# E75-2G4M20S-BEE-1_1.net
KiCad netlist of a schematic drawn in EAGLE
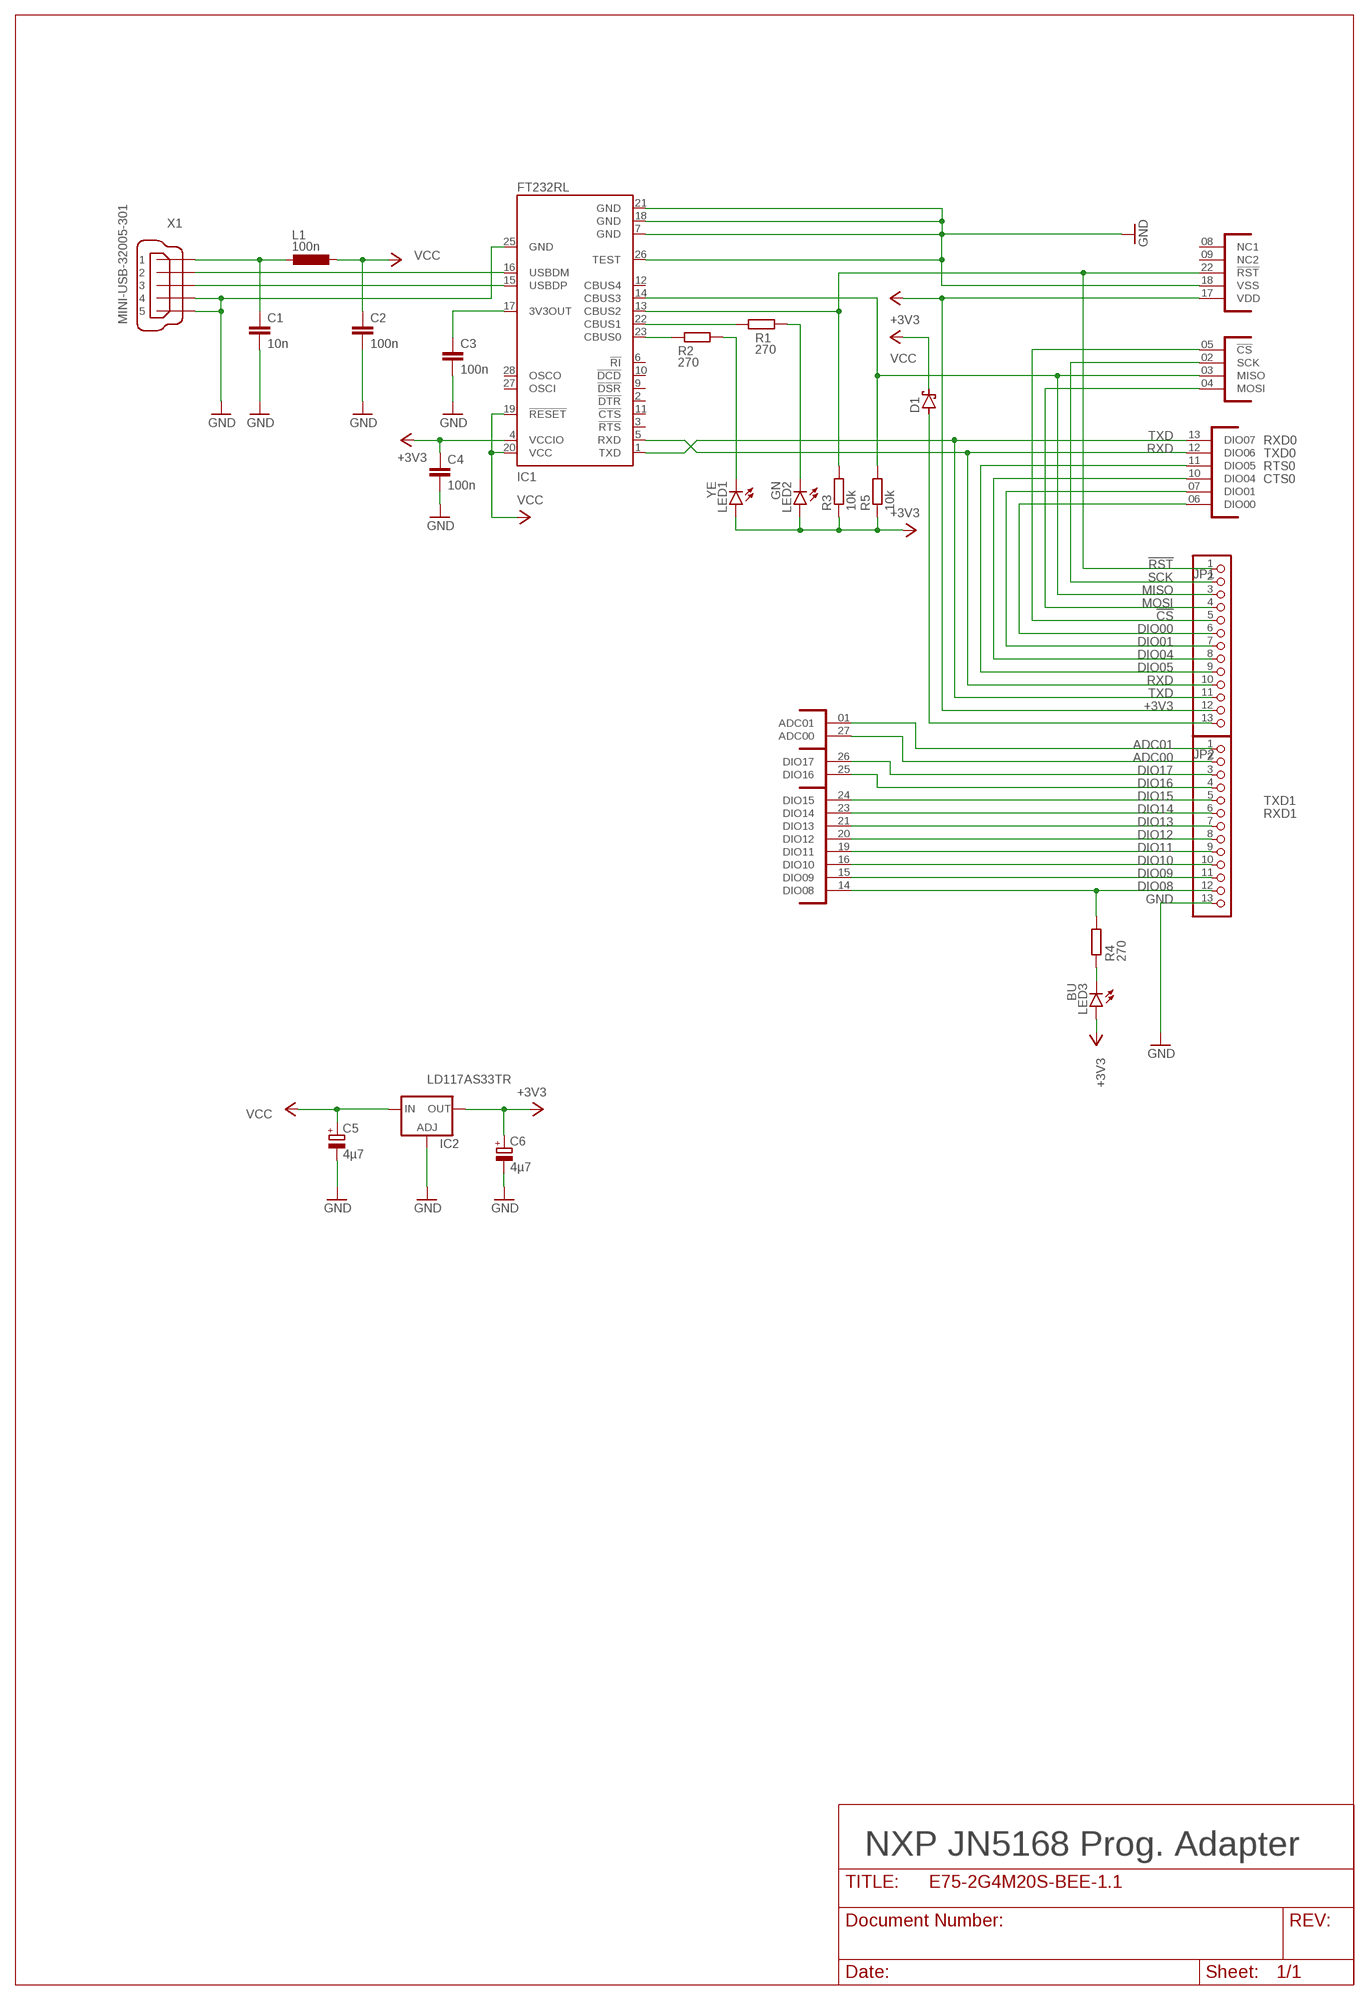
[diagram p0: schematic, sheet 1]

(export (version "E")
  (design (tool "Eeschema 10.0.6"))
  (components
    (comp (ref "C1")
      (value "10n")
      (footprint "eagle-import:C0805")
      (libsource (lib "eagle-import") (part "C-EUC0805"))
    )
    (comp (ref "C2")
      (value "100n")
      (footprint "eagle-import:C0805")
      (libsource (lib "eagle-import") (part "C-EUC0805"))
    )
    (comp (ref "C3")
      (value "100n")
      (footprint "eagle-import:C0805")
      (libsource (lib "eagle-import") (part "C-EUC0805"))
    )
    (comp (ref "C4")
      (value "100n")
      (footprint "eagle-import:C0805")
      (libsource (lib "eagle-import") (part "C-EUC0805"))
    )
    (comp (ref "C5")
      (value "4µ7")
      (footprint "eagle-import:SMC_B")
      (libsource (lib "eagle-import") (part "CPOL-EUSMCB"))
    )
    (comp (ref "C6")
      (value "4µ7")
      (footprint "eagle-import:SMC_B")
      (libsource (lib "eagle-import") (part "CPOL-EUSMCB"))
    )
    (comp (ref "D1")
      (value "SCHOTTKY-DIODESMD")
      (footprint "eagle-import:SMB")
      (libsource (lib "eagle-import") (part "SCHOTTKY-DIODESMD"))
    )
    (comp (ref "IC1")
      (value "FT232RL")
      (footprint "eagle-import:SSOP28")
      (libsource (lib "eagle-import") (part "FT232RL"))
    )
    (comp (ref "IC2")
      (value "LD117AS33TR")
      (footprint "eagle-import:SOT223")
      (libsource (lib "eagle-import") (part "LD117A?S33TR"))
    )
    (comp (ref "JP1")
      (value "PINHD-1X13")
      (footprint "eagle-import:1X13")
      (libsource (lib "eagle-import") (part "PINHD-1X13"))
    )
    (comp (ref "JP2")
      (value "PINHD-1X13")
      (footprint "eagle-import:1X13")
      (libsource (lib "eagle-import") (part "PINHD-1X13"))
    )
    (comp (ref "L1")
      (value "100n")
      (footprint "eagle-import:L3225P")
      (libsource (lib "eagle-import") (part "L-EUL3225P"))
    )
    (comp (ref "LED1")
      (value "YE")
      (footprint "eagle-import:CHIP-LED0805")
      (libsource (lib "eagle-import") (part "LEDCHIP-LED0805"))
    )
    (comp (ref "LED2")
      (value "GN")
      (footprint "eagle-import:CHIP-LED0805")
      (libsource (lib "eagle-import") (part "LEDCHIP-LED0805"))
    )
    (comp (ref "LED3")
      (value "BU")
      (footprint "eagle-import:CHIP-LED0805")
      (libsource (lib "eagle-import") (part "LEDCHIP-LED0805"))
    )
    (comp (ref "N1")
      (value "E75-2G4M20S")
      (footprint "eagle-import:E75-2G4M20S")
      (libsource (lib "eagle-import") (part "E75-2G4M20S"))
    )
    (comp (ref "R1")
      (value "270")
      (footprint "eagle-import:R0805W")
      (libsource (lib "eagle-import") (part "R-EU_R0805W"))
    )
    (comp (ref "R2")
      (value "270")
      (footprint "eagle-import:R0805W")
      (libsource (lib "eagle-import") (part "R-EU_R0805W"))
    )
    (comp (ref "R3")
      (value "10k")
      (footprint "eagle-import:M0805")
      (libsource (lib "eagle-import") (part "R-EU_M0805"))
    )
    (comp (ref "R4")
      (value "270")
      (footprint "eagle-import:R0805W")
      (libsource (lib "eagle-import") (part "R-EU_R0805W"))
    )
    (comp (ref "R5")
      (value "10k")
      (footprint "eagle-import:M0805")
      (libsource (lib "eagle-import") (part "R-EU_M0805"))
    )
    (comp (ref "X1")
      (value "MINI-USB-32005-301")
      (footprint "eagle-import:32005-301")
      (libsource (lib "eagle-import") (part "MINI-USB-32005-301"))
    )
  )
  (nets
    (net (code "1") (name "+3V3") (class "Default")
      (node (ref "C4") (pin "1") (pinfunction "1_1") (pintype "passive"))
      (node (ref "C6") (pin "+") (pinfunction "+_+") (pintype "passive"))
      (node (ref "IC1") (pin "4") (pinfunction "VCCIO_4") (pintype "power_in"))
      (node (ref "IC2") (pin "4") (pinfunction "OUT_4") (pintype "passive"))
      (node (ref "JP1") (pin "12") (pinfunction "12_12") (pintype "passive"))
      (node (ref "LED1") (pin "A") (pinfunction "A_A") (pintype "passive"))
      (node (ref "LED2") (pin "A") (pinfunction "A_A") (pintype "passive"))
      (node (ref "LED3") (pin "A") (pinfunction "A_A") (pintype "passive"))
      (node (ref "N1") (pin "17") (pinfunction "VDD_17") (pintype "bidirectional"))
      (node (ref "R3") (pin "1") (pinfunction "1_1") (pintype "passive"))
      (node (ref "R5") (pin "1") (pinfunction "1_1") (pintype "passive"))
    )
    (net (code "2") (name "/ADC00") (class "Default")
      (node (ref "JP2") (pin "2") (pinfunction "2_2") (pintype "passive"))
      (node (ref "N1") (pin "27") (pinfunction "ADC00_27") (pintype "bidirectional"))
    )
    (net (code "3") (name "/ADC01") (class "Default")
      (node (ref "JP2") (pin "1") (pinfunction "1_1") (pintype "passive"))
      (node (ref "N1") (pin "01") (pinfunction "ADC01_01") (pintype "bidirectional"))
    )
    (net (code "4") (name "/DIO00") (class "Default")
      (node (ref "JP1") (pin "6") (pinfunction "6_6") (pintype "passive"))
      (node (ref "N1") (pin "06") (pinfunction "DIO00_06") (pintype "bidirectional"))
    )
    (net (code "5") (name "/DIO01") (class "Default")
      (node (ref "JP1") (pin "7") (pinfunction "7_7") (pintype "passive"))
      (node (ref "N1") (pin "07") (pinfunction "DIO01_07") (pintype "bidirectional"))
    )
    (net (code "6") (name "/DIO04") (class "Default")
      (node (ref "JP1") (pin "8") (pinfunction "8_8") (pintype "passive"))
      (node (ref "N1") (pin "10") (pinfunction "DIO04_10") (pintype "bidirectional"))
    )
    (net (code "7") (name "/DIO05") (class "Default")
      (node (ref "JP1") (pin "9") (pinfunction "9_9") (pintype "passive"))
      (node (ref "N1") (pin "11") (pinfunction "DIO05_11") (pintype "bidirectional"))
    )
    (net (code "8") (name "/DIO08") (class "Default")
      (node (ref "JP2") (pin "12") (pinfunction "12_12") (pintype "passive"))
      (node (ref "N1") (pin "14") (pinfunction "DIO08_14") (pintype "bidirectional"))
      (node (ref "R4") (pin "2") (pinfunction "2_2") (pintype "passive"))
    )
    (net (code "9") (name "/DIO09") (class "Default")
      (node (ref "JP2") (pin "11") (pinfunction "11_11") (pintype "passive"))
      (node (ref "N1") (pin "15") (pinfunction "DIO09_15") (pintype "bidirectional"))
    )
    (net (code "10") (name "/DIO10") (class "Default")
      (node (ref "JP2") (pin "10") (pinfunction "10_10") (pintype "passive"))
      (node (ref "N1") (pin "16") (pinfunction "DIO10_16") (pintype "bidirectional"))
    )
    (net (code "11") (name "/DIO11") (class "Default")
      (node (ref "JP2") (pin "9") (pinfunction "9_9") (pintype "passive"))
      (node (ref "N1") (pin "19") (pinfunction "DIO11_19") (pintype "bidirectional"))
    )
    (net (code "12") (name "/DIO12") (class "Default")
      (node (ref "JP2") (pin "8") (pinfunction "8_8") (pintype "passive"))
      (node (ref "N1") (pin "20") (pinfunction "DIO12_20") (pintype "bidirectional"))
    )
    (net (code "13") (name "/DIO13") (class "Default")
      (node (ref "JP2") (pin "7") (pinfunction "7_7") (pintype "passive"))
      (node (ref "N1") (pin "21") (pinfunction "DIO13_21") (pintype "bidirectional"))
    )
    (net (code "14") (name "/DIO14") (class "Default")
      (node (ref "JP2") (pin "6") (pinfunction "6_6") (pintype "passive"))
      (node (ref "N1") (pin "23") (pinfunction "DIO14_23") (pintype "bidirectional"))
    )
    (net (code "15") (name "/DIO15") (class "Default")
      (node (ref "JP2") (pin "5") (pinfunction "5_5") (pintype "passive"))
      (node (ref "N1") (pin "24") (pinfunction "DIO15_24") (pintype "bidirectional"))
    )
    (net (code "16") (name "/DIO16") (class "Default")
      (node (ref "JP2") (pin "4") (pinfunction "4_4") (pintype "passive"))
      (node (ref "N1") (pin "25") (pinfunction "DIO16_25") (pintype "bidirectional"))
    )
    (net (code "17") (name "/DIO17") (class "Default")
      (node (ref "JP2") (pin "3") (pinfunction "3_3") (pintype "passive"))
      (node (ref "N1") (pin "26") (pinfunction "DIO17_26") (pintype "bidirectional"))
    )
    (net (code "18") (name "/MISO") (class "Default")
      (node (ref "IC1") (pin "14") (pinfunction "CBUS3_14") (pintype "bidirectional"))
      (node (ref "JP1") (pin "3") (pinfunction "3_3") (pintype "passive"))
      (node (ref "N1") (pin "03") (pinfunction "MISO_03") (pintype "bidirectional"))
      (node (ref "R5") (pin "2") (pinfunction "2_2") (pintype "passive"))
    )
    (net (code "19") (name "/MOSI") (class "Default")
      (node (ref "JP1") (pin "4") (pinfunction "4_4") (pintype "passive"))
      (node (ref "N1") (pin "04") (pinfunction "MOSI_04") (pintype "bidirectional"))
    )
    (net (code "20") (name "/RXD") (class "Default")
      (node (ref "IC1") (pin "5") (pinfunction "RXD_5") (pintype "input"))
      (node (ref "JP1") (pin "10") (pinfunction "10_10") (pintype "passive"))
      (node (ref "N1") (pin "12") (pinfunction "DIO06_12") (pintype "bidirectional"))
    )
    (net (code "21") (name "/SCK") (class "Default")
      (node (ref "JP1") (pin "2") (pinfunction "2_2") (pintype "passive"))
      (node (ref "N1") (pin "02") (pinfunction "SCK_02") (pintype "bidirectional"))
    )
    (net (code "22") (name "/TXD") (class "Default")
      (node (ref "IC1") (pin "1") (pinfunction "TXD_1") (pintype "output"))
      (node (ref "JP1") (pin "11") (pinfunction "11_11") (pintype "passive"))
      (node (ref "N1") (pin "13") (pinfunction "DIO07_13") (pintype "bidirectional"))
    )
    (net (code "23") (name "/~{CS}") (class "Default")
      (node (ref "JP1") (pin "5") (pinfunction "5_5") (pintype "passive"))
      (node (ref "N1") (pin "05") (pinfunction "~{CS}_05") (pintype "bidirectional"))
    )
    (net (code "24") (name "/~{RST}") (class "Default")
      (node (ref "IC1") (pin "13") (pinfunction "CBUS2_13") (pintype "bidirectional"))
      (node (ref "JP1") (pin "1") (pinfunction "1_1") (pintype "passive"))
      (node (ref "N1") (pin "22") (pinfunction "~{RST}_22") (pintype "bidirectional"))
      (node (ref "R3") (pin "2") (pinfunction "2_2") (pintype "passive"))
    )
    (net (code "25") (name "GND") (class "Default")
      (node (ref "C1") (pin "2") (pinfunction "2_2") (pintype "passive"))
      (node (ref "C2") (pin "2") (pinfunction "2_2") (pintype "passive"))
      (node (ref "C3") (pin "2") (pinfunction "2_2") (pintype "passive"))
      (node (ref "C4") (pin "2") (pinfunction "2_2") (pintype "passive"))
      (node (ref "C5") (pin "-") (pinfunction "-_-") (pintype "passive"))
      (node (ref "C6") (pin "-") (pinfunction "-_-") (pintype "passive"))
      (node (ref "IC1") (pin "18") (pinfunction "GND_18") (pintype "power_in"))
      (node (ref "IC1") (pin "21") (pinfunction "GND_21") (pintype "power_in"))
      (node (ref "IC1") (pin "25") (pinfunction "GND_25") (pintype "power_in"))
      (node (ref "IC1") (pin "26") (pinfunction "TEST_26") (pintype "input"))
      (node (ref "IC1") (pin "7") (pinfunction "GND_7") (pintype "power_in"))
      (node (ref "IC2") (pin "1") (pinfunction "ADJ_1") (pintype "input"))
      (node (ref "JP2") (pin "13") (pinfunction "13_13") (pintype "passive"))
      (node (ref "N1") (pin "18") (pinfunction "VSS_18") (pintype "bidirectional"))
      (node (ref "X1") (pin "4") (pinfunction "4_4") (pintype "passive"))
      (node (ref "X1") (pin "5") (pinfunction "5_5") (pintype "passive"))
    )
    (net (code "26") (name "Net-(C1-Pad1)") (class "Default")
      (node (ref "C1") (pin "1") (pinfunction "1_1") (pintype "passive"))
      (node (ref "L1") (pin "2") (pinfunction "2_2") (pintype "passive"))
      (node (ref "X1") (pin "1") (pinfunction "1_1") (pintype "passive"))
    )
    (net (code "27") (name "Net-(D1-PadA)") (class "Default")
      (node (ref "D1") (pin "A") (pinfunction "A_A") (pintype "passive"))
      (node (ref "JP1") (pin "13") (pinfunction "13_13") (pintype "passive"))
    )
    (net (code "28") (name "Net-(IC1-3V3OUT)") (class "Default")
      (node (ref "C3") (pin "1") (pinfunction "1_1") (pintype "passive"))
      (node (ref "IC1") (pin "17") (pinfunction "3V3OUT_17") (pintype "output"))
    )
    (net (code "29") (name "Net-(IC1-CBUS0)") (class "Default")
      (node (ref "IC1") (pin "23") (pinfunction "CBUS0_23") (pintype "bidirectional"))
      (node (ref "R2") (pin "1") (pinfunction "1_1") (pintype "passive"))
    )
    (net (code "30") (name "Net-(IC1-CBUS1)") (class "Default")
      (node (ref "IC1") (pin "22") (pinfunction "CBUS1_22") (pintype "bidirectional"))
      (node (ref "R1") (pin "1") (pinfunction "1_1") (pintype "passive"))
    )
    (net (code "31") (name "Net-(IC1-USBDM)") (class "Default")
      (node (ref "IC1") (pin "16") (pinfunction "USBDM_16") (pintype "bidirectional"))
      (node (ref "X1") (pin "2") (pinfunction "2_2") (pintype "passive"))
    )
    (net (code "32") (name "Net-(IC1-USBDP)") (class "Default")
      (node (ref "IC1") (pin "15") (pinfunction "USBDP_15") (pintype "bidirectional"))
      (node (ref "X1") (pin "3") (pinfunction "3_3") (pintype "passive"))
    )
    (net (code "33") (name "Net-(LED1-PadC)") (class "Default")
      (node (ref "LED1") (pin "C") (pinfunction "C_C") (pintype "passive"))
      (node (ref "R2") (pin "2") (pinfunction "2_2") (pintype "passive"))
    )
    (net (code "34") (name "Net-(LED2-PadC)") (class "Default")
      (node (ref "LED2") (pin "C") (pinfunction "C_C") (pintype "passive"))
      (node (ref "R1") (pin "2") (pinfunction "2_2") (pintype "passive"))
    )
    (net (code "35") (name "Net-(LED3-PadC)") (class "Default")
      (node (ref "LED3") (pin "C") (pinfunction "C_C") (pintype "passive"))
      (node (ref "R4") (pin "1") (pinfunction "1_1") (pintype "passive"))
    )
    (net (code "36") (name "VCC") (class "Default")
      (node (ref "C2") (pin "1") (pinfunction "1_1") (pintype "passive"))
      (node (ref "C5") (pin "+") (pinfunction "+_+") (pintype "passive"))
      (node (ref "D1") (pin "C") (pinfunction "C_C") (pintype "passive"))
      (node (ref "IC1") (pin "19") (pinfunction "~{RESET}_19") (pintype "input"))
      (node (ref "IC1") (pin "20") (pinfunction "VCC_20") (pintype "power_in"))
      (node (ref "IC2") (pin "3") (pinfunction "IN_3") (pintype "input"))
      (node (ref "L1") (pin "1") (pinfunction "1_1") (pintype "passive"))
    )
    (net (code "37") (name "unconnected-(IC1-CBUS4-Pad12)") (class "Default")
      (node (ref "IC1") (pin "12") (pinfunction "CBUS4_12") (pintype "bidirectional"))
    )
    (net (code "38") (name "unconnected-(IC1-OSCI-Pad27)") (class "Default")
      (node (ref "IC1") (pin "27") (pinfunction "OSCI_27") (pintype "input"))
    )
    (net (code "39") (name "unconnected-(IC1-OSCO-Pad28)") (class "Default")
      (node (ref "IC1") (pin "28") (pinfunction "OSCO_28") (pintype "output"))
    )
    (net (code "40") (name "unconnected-(IC1-~{CTS}-Pad11)") (class "Default")
      (node (ref "IC1") (pin "11") (pinfunction "~{CTS}_11") (pintype "input"))
    )
    (net (code "41") (name "unconnected-(IC1-~{DCD}-Pad10)") (class "Default")
      (node (ref "IC1") (pin "10") (pinfunction "~{DCD}_10") (pintype "input"))
    )
    (net (code "42") (name "unconnected-(IC1-~{DSR}-Pad9)") (class "Default")
      (node (ref "IC1") (pin "9") (pinfunction "~{DSR}_9") (pintype "input"))
    )
    (net (code "43") (name "unconnected-(IC1-~{DTR}-Pad2)") (class "Default")
      (node (ref "IC1") (pin "2") (pinfunction "~{DTR}_2") (pintype "output"))
    )
    (net (code "44") (name "unconnected-(IC1-~{RI}-Pad6)") (class "Default")
      (node (ref "IC1") (pin "6") (pinfunction "~{RI}_6") (pintype "input"))
    )
    (net (code "45") (name "unconnected-(IC1-~{RTS}-Pad3)") (class "Default")
      (node (ref "IC1") (pin "3") (pinfunction "~{RTS}_3") (pintype "output"))
    )
    (net (code "46") (name "unconnected-(N1F-NC1-Pad08)") (class "Default")
      (node (ref "N1") (pin "08") (pinfunction "NC1_08") (pintype "no_connect"))
    )
    (net (code "47") (name "unconnected-(N1F-NC2-Pad09)") (class "Default")
      (node (ref "N1") (pin "09") (pinfunction "NC2_09") (pintype "no_connect"))
    )
  )
)
